# Sheet1.net
KiCad netlist of a schematic drawn in Altium Designer
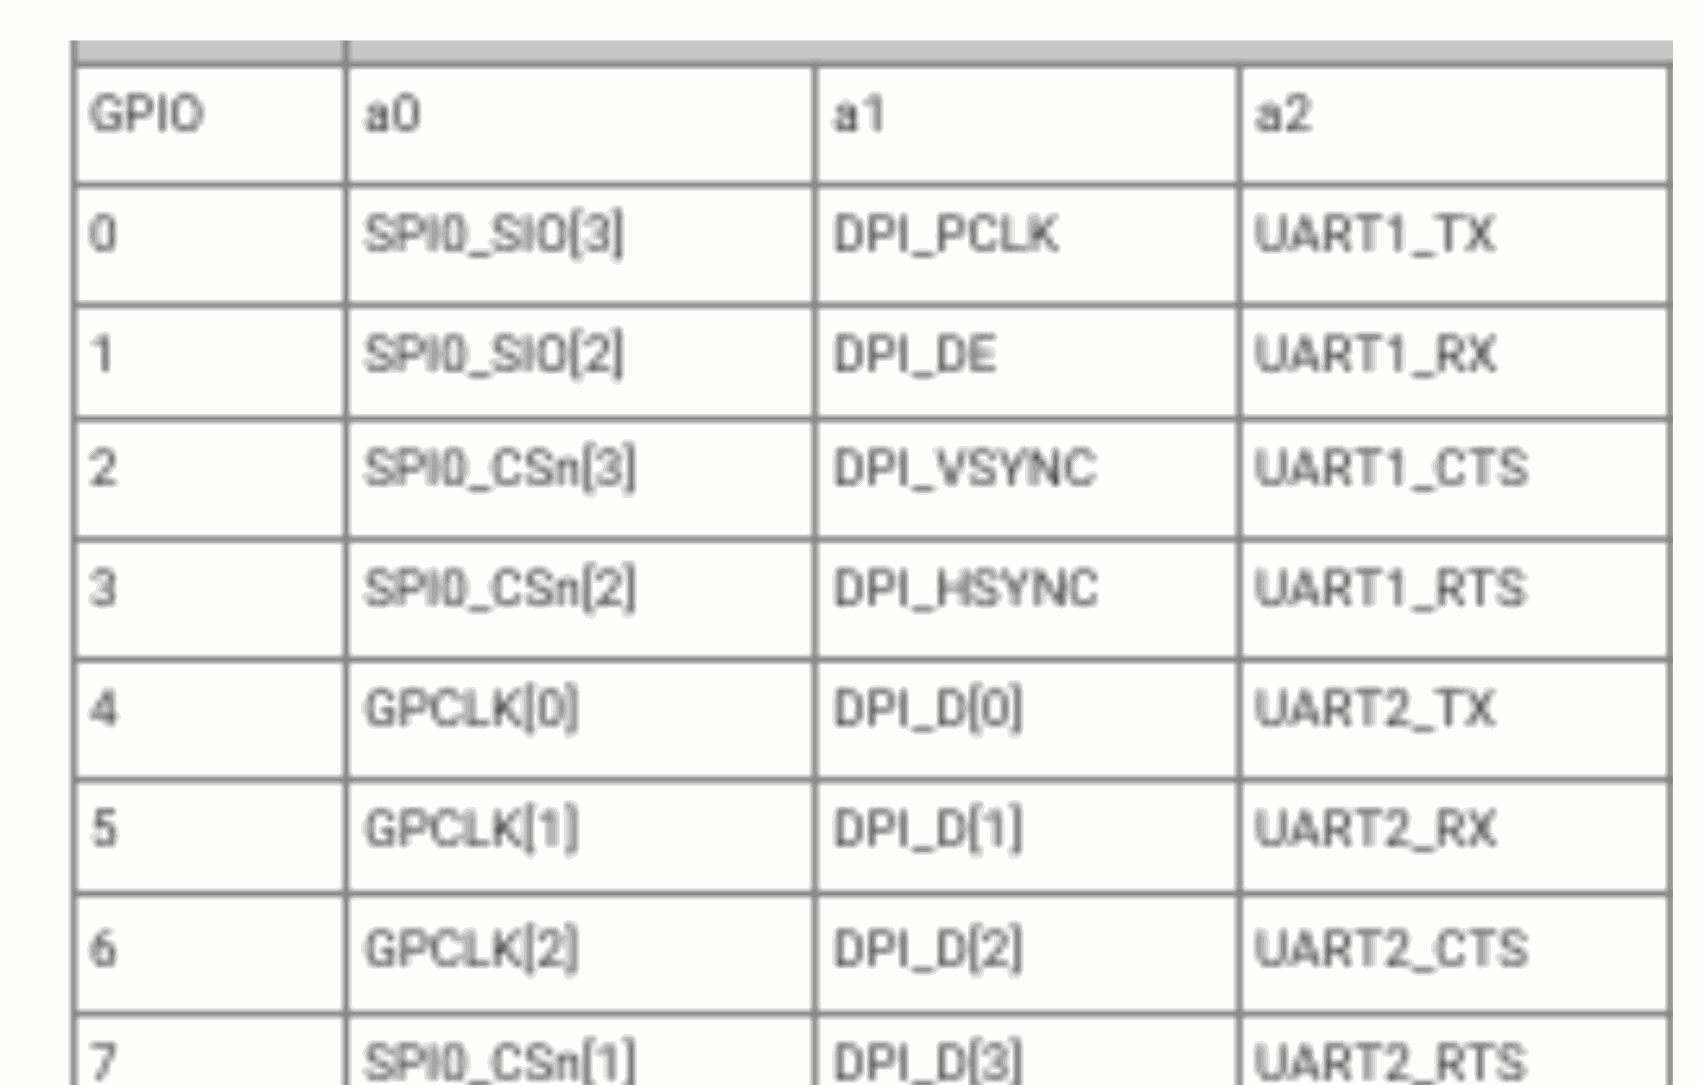
[diagram p0: Sheet1.SchDoc, top left]
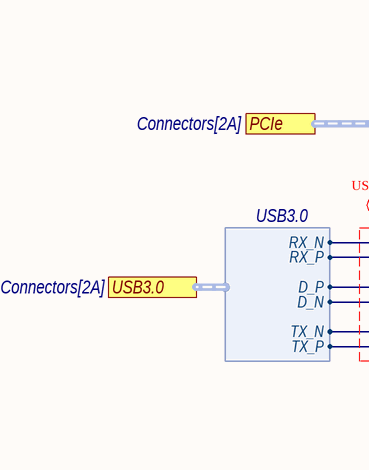
[diagram p1: Sheet1.SchDoc, top middle]
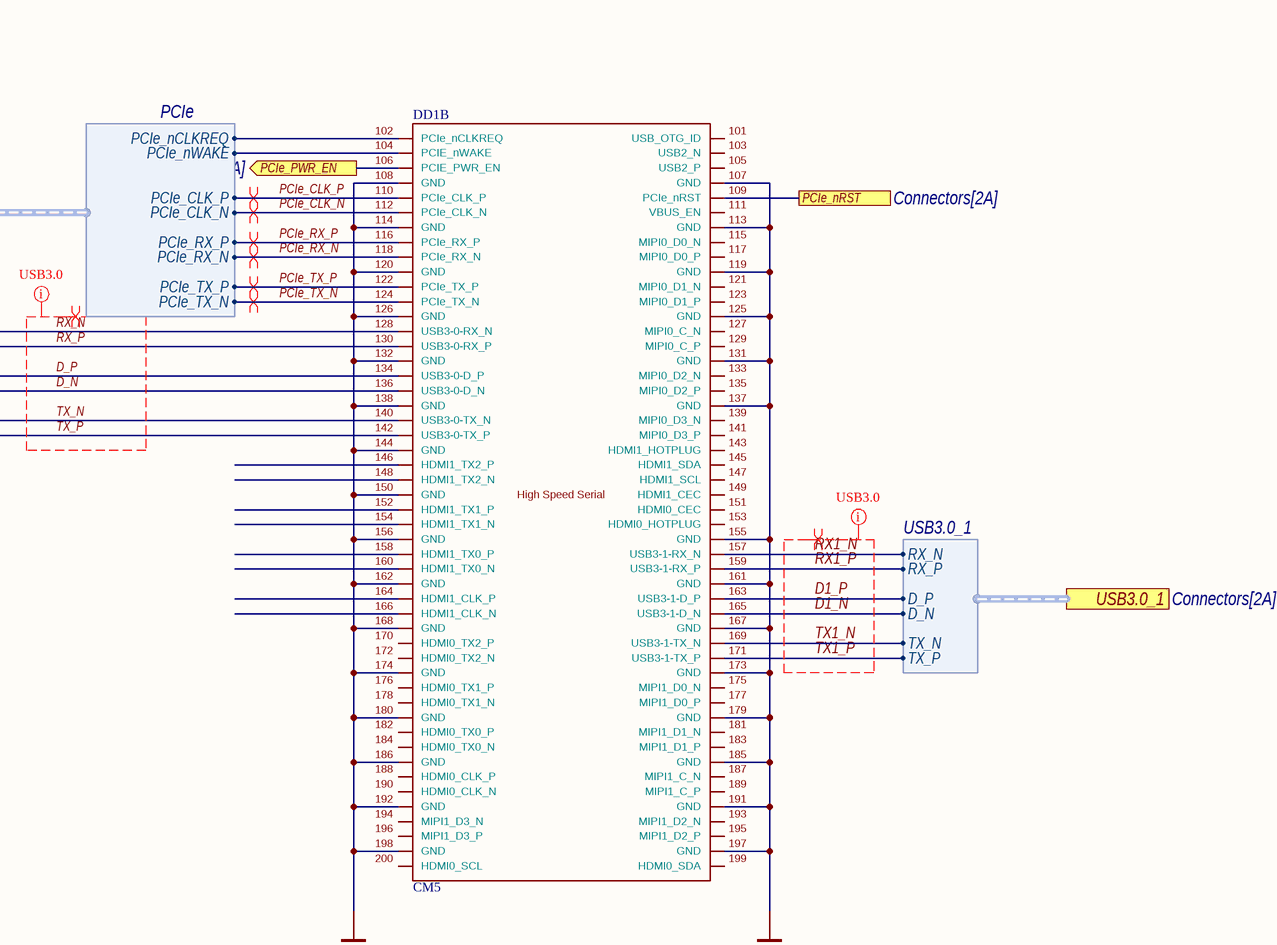
[diagram p2: Sheet1.SchDoc, top right]
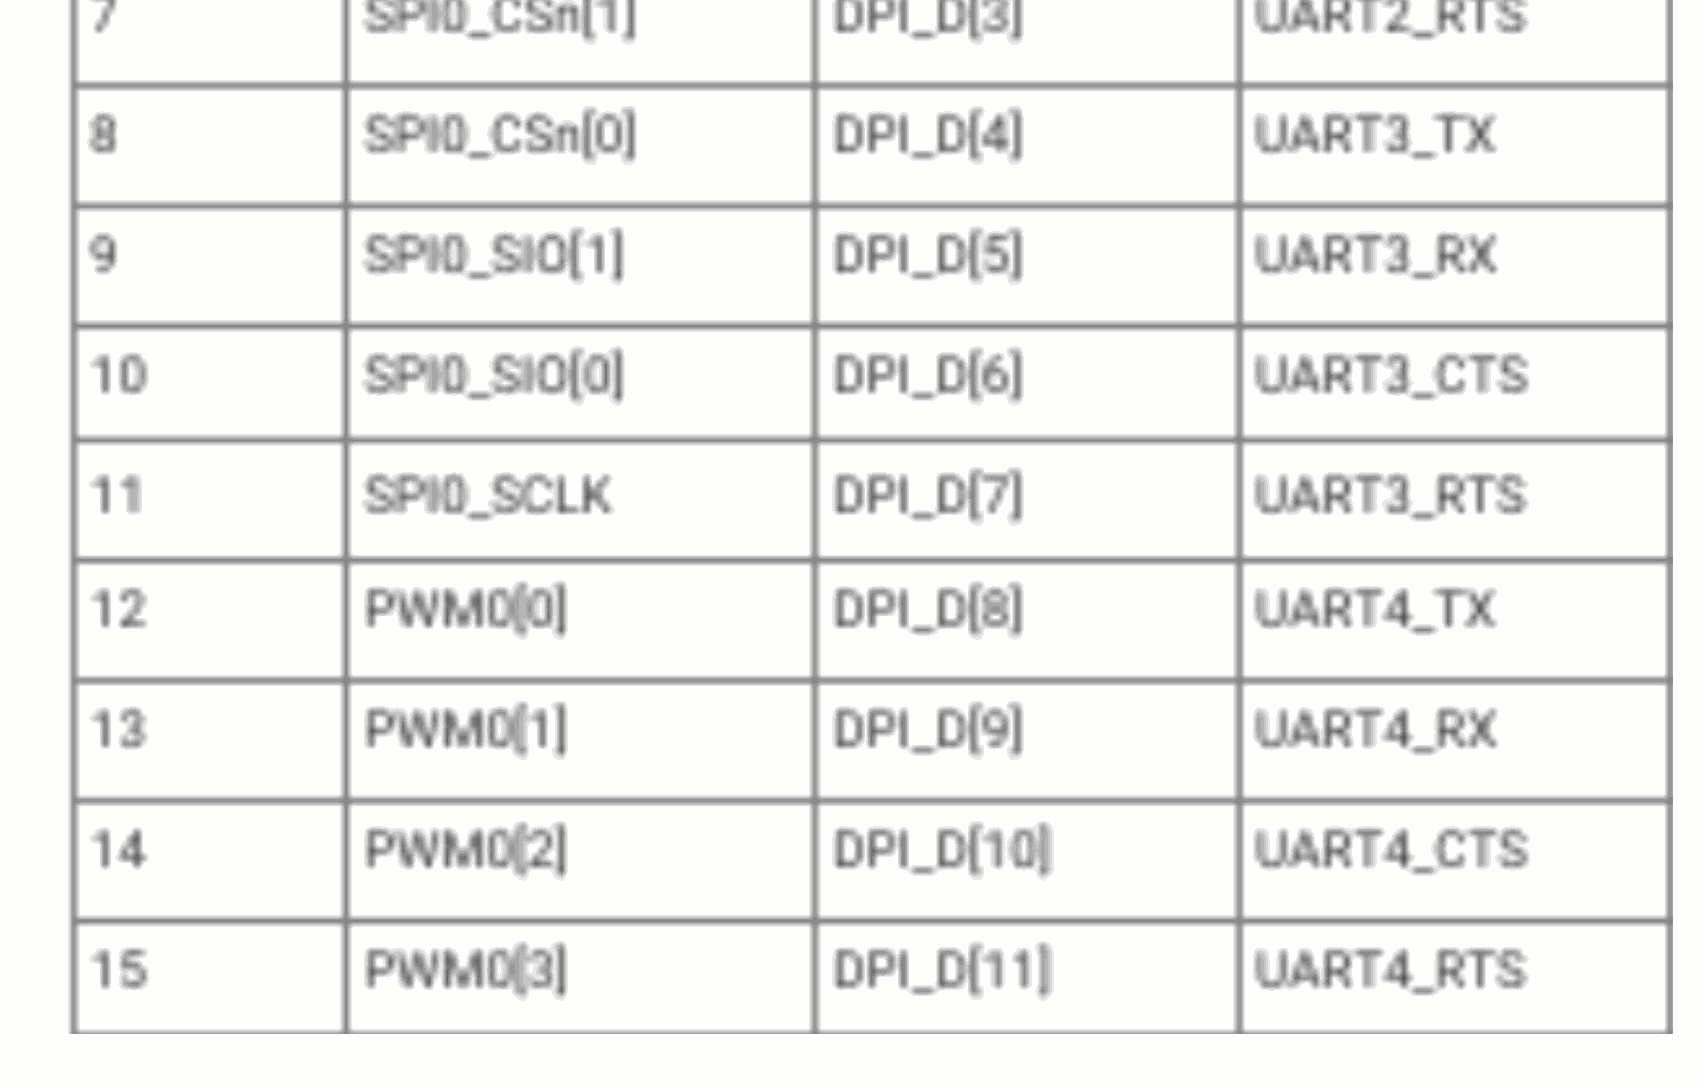
[diagram p3: Sheet1.SchDoc, bottom left]
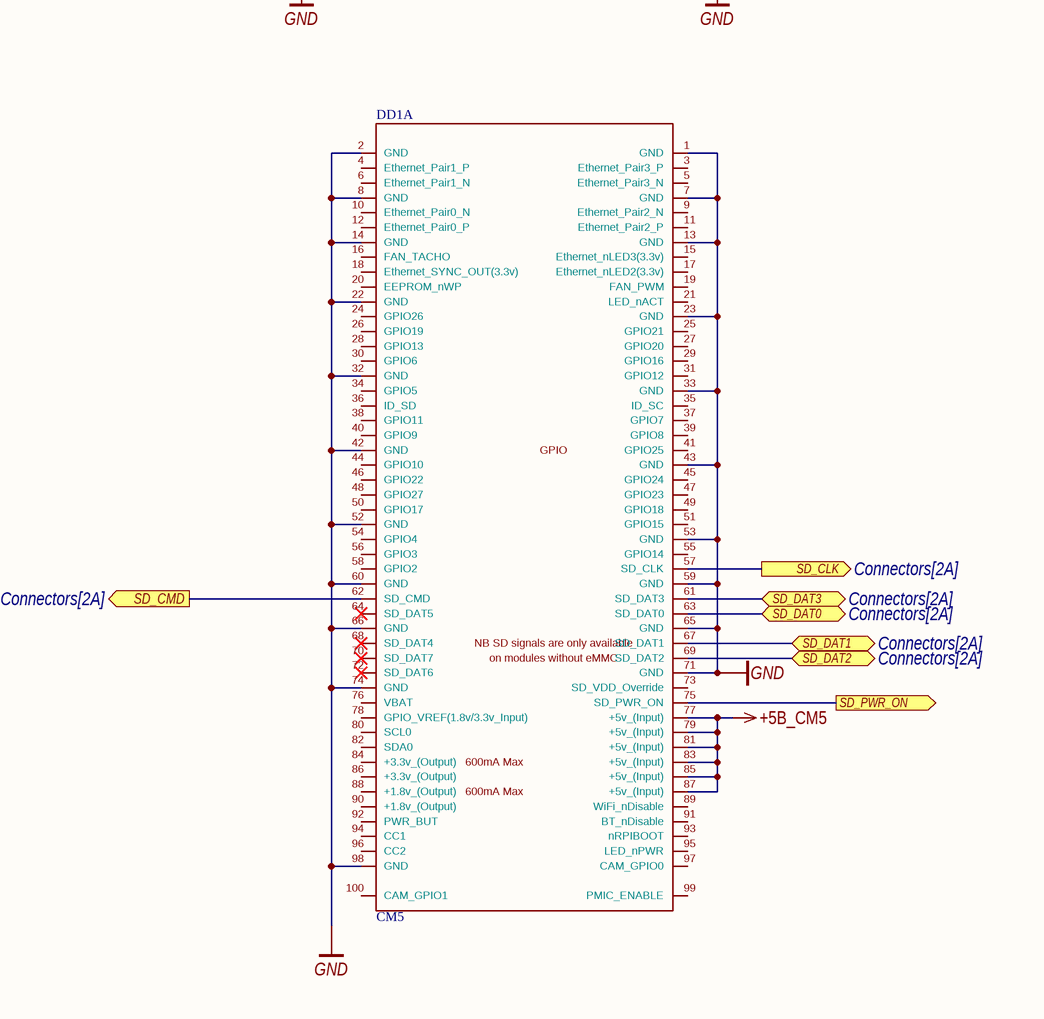
[diagram p4: Sheet1.SchDoc, bottom right]

(export (version "E")
  (design (tool "Eeschema 10.0.6"))
  (components
    (comp (ref "DD1")
      (value "CM5")
      (footprint "CM4-DF40HC(3.0)-100DS-0.4v_3mm_1.5mm")
      (libsource (lib "Hydrolib") (part "CM5"))
    )
  )
  (nets
    (net (code "4") (name "+5В_CM5") (class "Default")
      (node (ref "DD1") (pin "77") (pinfunction "+5v_(Input)_77") (pintype "passive"))
      (node (ref "DD1") (pin "79") (pinfunction "+5v_(Input)_79") (pintype "passive"))
      (node (ref "DD1") (pin "81") (pinfunction "+5v_(Input)_81") (pintype "passive"))
      (node (ref "DD1") (pin "83") (pinfunction "+5v_(Input)_83") (pintype "passive"))
      (node (ref "DD1") (pin "85") (pinfunction "+5v_(Input)_85") (pintype "passive"))
      (node (ref "DD1") (pin "87") (pinfunction "+5v_(Input)_87") (pintype "passive"))
    )
    (net (code "5") (name "/D1_N") (class "Default")
      (node (ref "DD1") (pin "165") (pinfunction "USB3-1-D_N_165") (pintype "passive"))
    )
    (net (code "6") (name "/D1_P") (class "Default")
      (node (ref "DD1") (pin "163") (pinfunction "USB3-1-D_P_163") (pintype "passive"))
    )
    (net (code "7") (name "/D_N") (class "Default")
      (node (ref "DD1") (pin "136") (pinfunction "USB3-0-D_N_136") (pintype "passive"))
    )
    (net (code "8") (name "/D_P") (class "Default")
      (node (ref "DD1") (pin "134") (pinfunction "USB3-0-D_P_134") (pintype "passive"))
    )
    (net (code "9") (name "/PCIe_CLK_N") (class "Default")
      (node (ref "DD1") (pin "112") (pinfunction "PCIe_CLK_N_112") (pintype "passive"))
    )
    (net (code "10") (name "/PCIe_CLK_P") (class "Default")
      (node (ref "DD1") (pin "110") (pinfunction "PCIe_CLK_P_110") (pintype "passive"))
    )
    (net (code "11") (name "/PCIe_PWR_EN") (class "Default")
      (node (ref "DD1") (pin "106") (pinfunction "PCIE_PWR_EN_106") (pintype "passive"))
    )
    (net (code "12") (name "/PCIe_RX_N") (class "Default")
      (node (ref "DD1") (pin "118") (pinfunction "PCIe_RX_N_118") (pintype "passive"))
    )
    (net (code "13") (name "/PCIe_RX_P") (class "Default")
      (node (ref "DD1") (pin "116") (pinfunction "PCIe_RX_P_116") (pintype "passive"))
    )
    (net (code "14") (name "/PCIe_TX_N") (class "Default")
      (node (ref "DD1") (pin "124") (pinfunction "PCIe_TX_N_124") (pintype "passive"))
    )
    (net (code "15") (name "/PCIe_TX_P") (class "Default")
      (node (ref "DD1") (pin "122") (pinfunction "PCIe_TX_P_122") (pintype "passive"))
    )
    (net (code "16") (name "/PCIe_nCLKREQ") (class "Default")
      (node (ref "DD1") (pin "102") (pinfunction "PCIe_nCLKREQ_102") (pintype "passive"))
    )
    (net (code "17") (name "/PCIe_nRST") (class "Default")
      (node (ref "DD1") (pin "109") (pinfunction "PCIe_nRST_109") (pintype "passive"))
    )
    (net (code "18") (name "/PCIe_nWAKE") (class "Default")
      (node (ref "DD1") (pin "104") (pinfunction "PCIE_nWAKE_104") (pintype "passive"))
    )
    (net (code "19") (name "/RX1_N") (class "Default")
      (node (ref "DD1") (pin "157") (pinfunction "USB3-1-RX_N_157") (pintype "passive"))
    )
    (net (code "20") (name "/RX1_P") (class "Default")
      (node (ref "DD1") (pin "159") (pinfunction "USB3-1-RX_P_159") (pintype "passive"))
    )
    (net (code "21") (name "/RX_N") (class "Default")
      (node (ref "DD1") (pin "128") (pinfunction "USB3-0-RX_N_128") (pintype "passive"))
    )
    (net (code "22") (name "/RX_P") (class "Default")
      (node (ref "DD1") (pin "130") (pinfunction "USB3-0-RX_P_130") (pintype "passive"))
    )
    (net (code "23") (name "/SD_CLK") (class "Default")
      (node (ref "DD1") (pin "57") (pinfunction "SD_CLK_57") (pintype "passive"))
    )
    (net (code "24") (name "/SD_CMD") (class "Default")
      (node (ref "DD1") (pin "62") (pinfunction "SD_CMD_62") (pintype "passive"))
    )
    (net (code "25") (name "/SD_DAT0") (class "Default")
      (node (ref "DD1") (pin "63") (pinfunction "SD_DAT0_63") (pintype "passive"))
    )
    (net (code "26") (name "/SD_DAT1") (class "Default")
      (node (ref "DD1") (pin "67") (pinfunction "SD_DAT1_67") (pintype "passive"))
    )
    (net (code "27") (name "/SD_DAT2") (class "Default")
      (node (ref "DD1") (pin "69") (pinfunction "SD_DAT2_69") (pintype "passive"))
    )
    (net (code "28") (name "/SD_DAT3") (class "Default")
      (node (ref "DD1") (pin "61") (pinfunction "SD_DAT3_61") (pintype "passive"))
    )
    (net (code "29") (name "/SD_PWR_ON") (class "Default")
      (node (ref "DD1") (pin "75") (pinfunction "SD_PWR_ON_75") (pintype "passive"))
    )
    (net (code "30") (name "/TX1_N") (class "Default")
      (node (ref "DD1") (pin "169") (pinfunction "USB3-1-TX_N_169") (pintype "passive"))
    )
    (net (code "31") (name "/TX1_P") (class "Default")
      (node (ref "DD1") (pin "171") (pinfunction "USB3-1-TX_P_171") (pintype "passive"))
    )
    (net (code "32") (name "/TX_N") (class "Default")
      (node (ref "DD1") (pin "140") (pinfunction "USB3-0-TX_N_140") (pintype "passive"))
    )
    (net (code "33") (name "/TX_P") (class "Default")
      (node (ref "DD1") (pin "142") (pinfunction "USB3-0-TX_P_142") (pintype "passive"))
    )
    (net (code "37") (name "GND") (class "Default")
      (node (ref "DD1") (pin "1") (pinfunction "GND_1") (pintype "passive"))
      (node (ref "DD1") (pin "107") (pinfunction "GND_107") (pintype "passive"))
      (node (ref "DD1") (pin "108") (pinfunction "GND_108") (pintype "passive"))
      (node (ref "DD1") (pin "113") (pinfunction "GND_113") (pintype "passive"))
      (node (ref "DD1") (pin "114") (pinfunction "GND_114") (pintype "passive"))
      (node (ref "DD1") (pin "119") (pinfunction "GND_119") (pintype "passive"))
      (node (ref "DD1") (pin "120") (pinfunction "GND_120") (pintype "passive"))
      (node (ref "DD1") (pin "125") (pinfunction "GND_125") (pintype "passive"))
      (node (ref "DD1") (pin "126") (pinfunction "GND_126") (pintype "passive"))
      (node (ref "DD1") (pin "13") (pinfunction "GND_13") (pintype "passive"))
      (node (ref "DD1") (pin "131") (pinfunction "GND_131") (pintype "passive"))
      (node (ref "DD1") (pin "132") (pinfunction "GND_132") (pintype "passive"))
      (node (ref "DD1") (pin "137") (pinfunction "GND_137") (pintype "passive"))
      (node (ref "DD1") (pin "138") (pinfunction "GND_138") (pintype "passive"))
      (node (ref "DD1") (pin "14") (pinfunction "GND_14") (pintype "passive"))
      (node (ref "DD1") (pin "144") (pinfunction "GND_144") (pintype "passive"))
      (node (ref "DD1") (pin "150") (pinfunction "GND_150") (pintype "passive"))
      (node (ref "DD1") (pin "155") (pinfunction "GND_155") (pintype "passive"))
      (node (ref "DD1") (pin "156") (pinfunction "GND_156") (pintype "passive"))
      (node (ref "DD1") (pin "161") (pinfunction "GND_161") (pintype "passive"))
      (node (ref "DD1") (pin "162") (pinfunction "GND_162") (pintype "passive"))
      (node (ref "DD1") (pin "167") (pinfunction "GND_167") (pintype "passive"))
      (node (ref "DD1") (pin "168") (pinfunction "GND_168") (pintype "passive"))
      (node (ref "DD1") (pin "173") (pinfunction "GND_173") (pintype "passive"))
      (node (ref "DD1") (pin "174") (pinfunction "GND_174") (pintype "passive"))
      (node (ref "DD1") (pin "179") (pinfunction "GND_179") (pintype "passive"))
      (node (ref "DD1") (pin "180") (pinfunction "GND_180") (pintype "passive"))
      (node (ref "DD1") (pin "185") (pinfunction "GND_185") (pintype "passive"))
      (node (ref "DD1") (pin "186") (pinfunction "GND_186") (pintype "passive"))
      (node (ref "DD1") (pin "191") (pinfunction "GND_191") (pintype "passive"))
      (node (ref "DD1") (pin "192") (pinfunction "GND_192") (pintype "passive"))
      (node (ref "DD1") (pin "197") (pinfunction "GND_197") (pintype "passive"))
      (node (ref "DD1") (pin "198") (pinfunction "GND_198") (pintype "passive"))
      (node (ref "DD1") (pin "2") (pinfunction "GND_2") (pintype "passive"))
      (node (ref "DD1") (pin "22") (pinfunction "GND_22") (pintype "passive"))
      (node (ref "DD1") (pin "23") (pinfunction "GND_23") (pintype "passive"))
      (node (ref "DD1") (pin "32") (pinfunction "GND_32") (pintype "passive"))
      (node (ref "DD1") (pin "33") (pinfunction "GND_33") (pintype "passive"))
      (node (ref "DD1") (pin "42") (pinfunction "GND_42") (pintype "passive"))
      (node (ref "DD1") (pin "43") (pinfunction "GND_43") (pintype "passive"))
      (node (ref "DD1") (pin "52") (pinfunction "GND_52") (pintype "passive"))
      (node (ref "DD1") (pin "53") (pinfunction "GND_53") (pintype "passive"))
      (node (ref "DD1") (pin "59") (pinfunction "GND_59") (pintype "passive"))
      (node (ref "DD1") (pin "60") (pinfunction "GND_60") (pintype "passive"))
      (node (ref "DD1") (pin "65") (pinfunction "GND_65") (pintype "passive"))
      (node (ref "DD1") (pin "66") (pinfunction "GND_66") (pintype "passive"))
      (node (ref "DD1") (pin "7") (pinfunction "GND_7") (pintype "passive"))
      (node (ref "DD1") (pin "71") (pinfunction "GND_71") (pintype "passive"))
      (node (ref "DD1") (pin "74") (pinfunction "GND_74") (pintype "passive"))
      (node (ref "DD1") (pin "8") (pinfunction "GND_8") (pintype "passive"))
      (node (ref "DD1") (pin "98") (pinfunction "GND_98") (pintype "passive"))
    )
    (net (code "38") (name "unconnected-(DD1A-+1.8v_(Output)-Pad88)") (class "Default")
      (node (ref "DD1") (pin "88") (pinfunction "+1.8v_(Output)_88") (pintype "passive"))
    )
    (net (code "39") (name "unconnected-(DD1A-+1.8v_(Output)-Pad90)") (class "Default")
      (node (ref "DD1") (pin "90") (pinfunction "+1.8v_(Output)_90") (pintype "passive"))
    )
    (net (code "40") (name "unconnected-(DD1A-+3.3v_(Output)-Pad84)") (class "Default")
      (node (ref "DD1") (pin "84") (pinfunction "+3.3v_(Output)_84") (pintype "passive"))
    )
    (net (code "41") (name "unconnected-(DD1A-+3.3v_(Output)-Pad86)") (class "Default")
      (node (ref "DD1") (pin "86") (pinfunction "+3.3v_(Output)_86") (pintype "passive"))
    )
    (net (code "42") (name "unconnected-(DD1A-BT_nDisable-Pad91)") (class "Default")
      (node (ref "DD1") (pin "91") (pinfunction "BT_nDisable_91") (pintype "passive"))
    )
    (net (code "43") (name "unconnected-(DD1A-CAM_GPIO0-Pad97)") (class "Default")
      (node (ref "DD1") (pin "97") (pinfunction "CAM_GPIO0_97") (pintype "passive"))
    )
    (net (code "44") (name "unconnected-(DD1A-CAM_GPIO1-Pad100)") (class "Default")
      (node (ref "DD1") (pin "100") (pinfunction "CAM_GPIO1_100") (pintype "passive"))
    )
    (net (code "45") (name "unconnected-(DD1A-CC1-Pad94)") (class "Default")
      (node (ref "DD1") (pin "94") (pinfunction "CC1_94") (pintype "passive"))
    )
    (net (code "46") (name "unconnected-(DD1A-CC2-Pad96)") (class "Default")
      (node (ref "DD1") (pin "96") (pinfunction "CC2_96") (pintype "passive"))
    )
    (net (code "47") (name "unconnected-(DD1A-EEPROM_nWP-Pad20)") (class "Default")
      (node (ref "DD1") (pin "20") (pinfunction "EEPROM_nWP_20") (pintype "passive"))
    )
    (net (code "48") (name "unconnected-(DD1A-Ethernet_Pair0_N-Pad10)") (class "Default")
      (node (ref "DD1") (pin "10") (pinfunction "Ethernet_Pair0_N_10") (pintype "passive"))
    )
    (net (code "49") (name "unconnected-(DD1A-Ethernet_Pair0_P-Pad12)") (class "Default")
      (node (ref "DD1") (pin "12") (pinfunction "Ethernet_Pair0_P_12") (pintype "passive"))
    )
    (net (code "50") (name "unconnected-(DD1A-Ethernet_Pair1_N-Pad6)") (class "Default")
      (node (ref "DD1") (pin "6") (pinfunction "Ethernet_Pair1_N_6") (pintype "passive"))
    )
    (net (code "51") (name "unconnected-(DD1A-Ethernet_Pair1_P-Pad4)") (class "Default")
      (node (ref "DD1") (pin "4") (pinfunction "Ethernet_Pair1_P_4") (pintype "passive"))
    )
    (net (code "52") (name "unconnected-(DD1A-Ethernet_Pair2_N-Pad9)") (class "Default")
      (node (ref "DD1") (pin "9") (pinfunction "Ethernet_Pair2_N_9") (pintype "passive"))
    )
    (net (code "53") (name "unconnected-(DD1A-Ethernet_Pair2_P-Pad11)") (class "Default")
      (node (ref "DD1") (pin "11") (pinfunction "Ethernet_Pair2_P_11") (pintype "passive"))
    )
    (net (code "54") (name "unconnected-(DD1A-Ethernet_Pair3_N-Pad5)") (class "Default")
      (node (ref "DD1") (pin "5") (pinfunction "Ethernet_Pair3_N_5") (pintype "passive"))
    )
    (net (code "55") (name "unconnected-(DD1A-Ethernet_Pair3_P-Pad3)") (class "Default")
      (node (ref "DD1") (pin "3") (pinfunction "Ethernet_Pair3_P_3") (pintype "passive"))
    )
    (net (code "56") (name "unconnected-(DD1A-Ethernet_SYNC_OUT(3.3v)-Pad18)") (class "Default")
      (node (ref "DD1") (pin "18") (pinfunction "Ethernet_SYNC_OUT(3.3v)_18") (pintype "passive"))
    )
    (net (code "57") (name "unconnected-(DD1A-Ethernet_nLED2(3.3v)-Pad17)") (class "Default")
      (node (ref "DD1") (pin "17") (pinfunction "Ethernet_nLED2(3.3v)_17") (pintype "passive"))
    )
    (net (code "58") (name "unconnected-(DD1A-Ethernet_nLED3(3.3v)-Pad15)") (class "Default")
      (node (ref "DD1") (pin "15") (pinfunction "Ethernet_nLED3(3.3v)_15") (pintype "passive"))
    )
    (net (code "59") (name "unconnected-(DD1A-FAN_PWM-Pad19)") (class "Default")
      (node (ref "DD1") (pin "19") (pinfunction "FAN_PWM_19") (pintype "passive"))
    )
    (net (code "60") (name "unconnected-(DD1A-FAN_TACHO-Pad16)") (class "Default")
      (node (ref "DD1") (pin "16") (pinfunction "FAN_TACHO_16") (pintype "passive"))
    )
    (net (code "61") (name "unconnected-(DD1A-GPIO2-Pad58)") (class "Default")
      (node (ref "DD1") (pin "58") (pinfunction "GPIO2_58") (pintype "passive"))
    )
    (net (code "62") (name "unconnected-(DD1A-GPIO3-Pad56)") (class "Default")
      (node (ref "DD1") (pin "56") (pinfunction "GPIO3_56") (pintype "passive"))
    )
    (net (code "63") (name "unconnected-(DD1A-GPIO4-Pad54)") (class "Default")
      (node (ref "DD1") (pin "54") (pinfunction "GPIO4_54") (pintype "passive"))
    )
    (net (code "64") (name "unconnected-(DD1A-GPIO5-Pad34)") (class "Default")
      (node (ref "DD1") (pin "34") (pinfunction "GPIO5_34") (pintype "passive"))
    )
    (net (code "65") (name "unconnected-(DD1A-GPIO6-Pad30)") (class "Default")
      (node (ref "DD1") (pin "30") (pinfunction "GPIO6_30") (pintype "passive"))
    )
    (net (code "66") (name "unconnected-(DD1A-GPIO7-Pad37)") (class "Default")
      (node (ref "DD1") (pin "37") (pinfunction "GPIO7_37") (pintype "passive"))
    )
    (net (code "67") (name "unconnected-(DD1A-GPIO8-Pad39)") (class "Default")
      (node (ref "DD1") (pin "39") (pinfunction "GPIO8_39") (pintype "passive"))
    )
    (net (code "68") (name "unconnected-(DD1A-GPIO9-Pad40)") (class "Default")
      (node (ref "DD1") (pin "40") (pinfunction "GPIO9_40") (pintype "passive"))
    )
    (net (code "69") (name "unconnected-(DD1A-GPIO10-Pad44)") (class "Default")
      (node (ref "DD1") (pin "44") (pinfunction "GPIO10_44") (pintype "passive"))
    )
    (net (code "70") (name "unconnected-(DD1A-GPIO11-Pad38)") (class "Default")
      (node (ref "DD1") (pin "38") (pinfunction "GPIO11_38") (pintype "passive"))
    )
    (net (code "71") (name "unconnected-(DD1A-GPIO12-Pad31)") (class "Default")
      (node (ref "DD1") (pin "31") (pinfunction "GPIO12_31") (pintype "passive"))
    )
    (net (code "72") (name "unconnected-(DD1A-GPIO13-Pad28)") (class "Default")
      (node (ref "DD1") (pin "28") (pinfunction "GPIO13_28") (pintype "passive"))
    )
    (net (code "73") (name "unconnected-(DD1A-GPIO14-Pad55)") (class "Default")
      (node (ref "DD1") (pin "55") (pinfunction "GPIO14_55") (pintype "passive"))
    )
    (net (code "74") (name "unconnected-(DD1A-GPIO15-Pad51)") (class "Default")
      (node (ref "DD1") (pin "51") (pinfunction "GPIO15_51") (pintype "passive"))
    )
    (net (code "75") (name "unconnected-(DD1A-GPIO16-Pad29)") (class "Default")
      (node (ref "DD1") (pin "29") (pinfunction "GPIO16_29") (pintype "passive"))
    )
    (net (code "76") (name "unconnected-(DD1A-GPIO17-Pad50)") (class "Default")
      (node (ref "DD1") (pin "50") (pinfunction "GPIO17_50") (pintype "passive"))
    )
    (net (code "77") (name "unconnected-(DD1A-GPIO18-Pad49)") (class "Default")
      (node (ref "DD1") (pin "49") (pinfunction "GPIO18_49") (pintype "passive"))
    )
    (net (code "78") (name "unconnected-(DD1A-GPIO19-Pad26)") (class "Default")
      (node (ref "DD1") (pin "26") (pinfunction "GPIO19_26") (pintype "passive"))
    )
    (net (code "79") (name "unconnected-(DD1A-GPIO20-Pad27)") (class "Default")
      (node (ref "DD1") (pin "27") (pinfunction "GPIO20_27") (pintype "passive"))
    )
    (net (code "80") (name "unconnected-(DD1A-GPIO21-Pad25)") (class "Default")
      (node (ref "DD1") (pin "25") (pinfunction "GPIO21_25") (pintype "passive"))
    )
    (net (code "81") (name "unconnected-(DD1A-GPIO22-Pad46)") (class "Default")
      (node (ref "DD1") (pin "46") (pinfunction "GPIO22_46") (pintype "passive"))
    )
    (net (code "82") (name "unconnected-(DD1A-GPIO23-Pad47)") (class "Default")
      (node (ref "DD1") (pin "47") (pinfunction "GPIO23_47") (pintype "passive"))
    )
    (net (code "83") (name "unconnected-(DD1A-GPIO24-Pad45)") (class "Default")
      (node (ref "DD1") (pin "45") (pinfunction "GPIO24_45") (pintype "passive"))
    )
    (net (code "84") (name "unconnected-(DD1A-GPIO25-Pad41)") (class "Default")
      (node (ref "DD1") (pin "41") (pinfunction "GPIO25_41") (pintype "passive"))
    )
    (net (code "85") (name "unconnected-(DD1A-GPIO26-Pad24)") (class "Default")
      (node (ref "DD1") (pin "24") (pinfunction "GPIO26_24") (pintype "passive"))
    )
    (net (code "86") (name "unconnected-(DD1A-GPIO27-Pad48)") (class "Default")
      (node (ref "DD1") (pin "48") (pinfunction "GPIO27_48") (pintype "passive"))
    )
    (net (code "87") (name "unconnected-(DD1A-GPIO_VREF(1.8v{slash}3.3v_Input)-Pad78)") (class "Default")
      (node (ref "DD1") (pin "78") (pinfunction "GPIO_VREF(1.8v/3.3v_Input)_78") (pintype "passive"))
    )
    (net (code "88") (name "unconnected-(DD1A-ID_SC-Pad35)") (class "Default")
      (node (ref "DD1") (pin "35") (pinfunction "ID_SC_35") (pintype "passive"))
    )
    (net (code "89") (name "unconnected-(DD1A-ID_SD-Pad36)") (class "Default")
      (node (ref "DD1") (pin "36") (pinfunction "ID_SD_36") (pintype "passive"))
    )
    (net (code "90") (name "unconnected-(DD1A-LED_nACT-Pad21)") (class "Default")
      (node (ref "DD1") (pin "21") (pinfunction "LED_nACT_21") (pintype "passive"))
    )
    (net (code "91") (name "unconnected-(DD1A-LED_nPWR-Pad95)") (class "Default")
      (node (ref "DD1") (pin "95") (pinfunction "LED_nPWR_95") (pintype "passive"))
    )
    (net (code "92") (name "unconnected-(DD1A-PMIC_ENABLE-Pad99)") (class "Default")
      (node (ref "DD1") (pin "99") (pinfunction "PMIC_ENABLE_99") (pintype "passive"))
    )
    (net (code "93") (name "unconnected-(DD1A-PWR_BUT-Pad92)") (class "Default")
      (node (ref "DD1") (pin "92") (pinfunction "PWR_BUT_92") (pintype "passive"))
    )
    (net (code "94") (name "unconnected-(DD1A-SCL0-Pad80)") (class "Default")
      (node (ref "DD1") (pin "80") (pinfunction "SCL0_80") (pintype "passive"))
    )
    (net (code "95") (name "unconnected-(DD1A-SDA0-Pad82)") (class "Default")
      (node (ref "DD1") (pin "82") (pinfunction "SDA0_82") (pintype "passive"))
    )
    (net (code "96") (name "unconnected-(DD1A-SD_DAT4-Pad68)") (class "Default")
      (node (ref "DD1") (pin "68") (pinfunction "SD_DAT4_68") (pintype "passive+no_connect"))
    )
    (net (code "97") (name "unconnected-(DD1A-SD_DAT5-Pad64)") (class "Default")
      (node (ref "DD1") (pin "64") (pinfunction "SD_DAT5_64") (pintype "passive+no_connect"))
    )
    (net (code "98") (name "unconnected-(DD1A-SD_DAT6-Pad72)") (class "Default")
      (node (ref "DD1") (pin "72") (pinfunction "SD_DAT6_72") (pintype "passive+no_connect"))
    )
    (net (code "99") (name "unconnected-(DD1A-SD_DAT7-Pad70)") (class "Default")
      (node (ref "DD1") (pin "70") (pinfunction "SD_DAT7_70") (pintype "passive+no_connect"))
    )
    (net (code "100") (name "unconnected-(DD1A-SD_VDD_Override-Pad73)") (class "Default")
      (node (ref "DD1") (pin "73") (pinfunction "SD_VDD_Override_73") (pintype "passive"))
    )
    (net (code "101") (name "unconnected-(DD1A-VBAT-Pad76)") (class "Default")
      (node (ref "DD1") (pin "76") (pinfunction "VBAT_76") (pintype "passive"))
    )
    (net (code "102") (name "unconnected-(DD1A-WiFi_nDisable-Pad89)") (class "Default")
      (node (ref "DD1") (pin "89") (pinfunction "WiFi_nDisable_89") (pintype "passive"))
    )
    (net (code "103") (name "unconnected-(DD1A-nRPIBOOT-Pad93)") (class "Default")
      (node (ref "DD1") (pin "93") (pinfunction "nRPIBOOT_93") (pintype "passive"))
    )
    (net (code "104") (name "unconnected-(DD1B-HDMI0_CEC-Pad151)") (class "Default")
      (node (ref "DD1") (pin "151") (pinfunction "HDMI0_CEC_151") (pintype "passive"))
    )
    (net (code "105") (name "unconnected-(DD1B-HDMI0_CLK_N-Pad190)") (class "Default")
      (node (ref "DD1") (pin "190") (pinfunction "HDMI0_CLK_N_190") (pintype "passive"))
    )
    (net (code "106") (name "unconnected-(DD1B-HDMI0_CLK_P-Pad188)") (class "Default")
      (node (ref "DD1") (pin "188") (pinfunction "HDMI0_CLK_P_188") (pintype "passive"))
    )
    (net (code "107") (name "unconnected-(DD1B-HDMI0_HOTPLUG-Pad153)") (class "Default")
      (node (ref "DD1") (pin "153") (pinfunction "HDMI0_HOTPLUG_153") (pintype "passive"))
    )
    (net (code "108") (name "unconnected-(DD1B-HDMI0_SCL-Pad200)") (class "Default")
      (node (ref "DD1") (pin "200") (pinfunction "HDMI0_SCL_200") (pintype "passive"))
    )
    (net (code "109") (name "unconnected-(DD1B-HDMI0_SDA-Pad199)") (class "Default")
      (node (ref "DD1") (pin "199") (pinfunction "HDMI0_SDA_199") (pintype "passive"))
    )
    (net (code "110") (name "unconnected-(DD1B-HDMI0_TX0_N-Pad184)") (class "Default")
      (node (ref "DD1") (pin "184") (pinfunction "HDMI0_TX0_N_184") (pintype "passive"))
    )
    (net (code "111") (name "unconnected-(DD1B-HDMI0_TX0_P-Pad182)") (class "Default")
      (node (ref "DD1") (pin "182") (pinfunction "HDMI0_TX0_P_182") (pintype "passive"))
    )
    (net (code "112") (name "unconnected-(DD1B-HDMI0_TX1_N-Pad178)") (class "Default")
      (node (ref "DD1") (pin "178") (pinfunction "HDMI0_TX1_N_178") (pintype "passive"))
    )
    (net (code "113") (name "unconnected-(DD1B-HDMI0_TX1_P-Pad176)") (class "Default")
      (node (ref "DD1") (pin "176") (pinfunction "HDMI0_TX1_P_176") (pintype "passive"))
    )
    (net (code "114") (name "unconnected-(DD1B-HDMI0_TX2_N-Pad172)") (class "Default")
      (node (ref "DD1") (pin "172") (pinfunction "HDMI0_TX2_N_172") (pintype "passive"))
    )
    (net (code "115") (name "unconnected-(DD1B-HDMI0_TX2_P-Pad170)") (class "Default")
      (node (ref "DD1") (pin "170") (pinfunction "HDMI0_TX2_P_170") (pintype "passive"))
    )
    (net (code "116") (name "unconnected-(DD1B-HDMI1_CEC-Pad149)") (class "Default")
      (node (ref "DD1") (pin "149") (pinfunction "HDMI1_CEC_149") (pintype "passive"))
    )
    (net (code "117") (name "unconnected-(DD1B-HDMI1_CLK_N-Pad166)") (class "Default")
      (node (ref "DD1") (pin "166") (pinfunction "HDMI1_CLK_N_166") (pintype "passive"))
    )
    (net (code "118") (name "unconnected-(DD1B-HDMI1_CLK_P-Pad164)") (class "Default")
      (node (ref "DD1") (pin "164") (pinfunction "HDMI1_CLK_P_164") (pintype "passive"))
    )
    (net (code "119") (name "unconnected-(DD1B-HDMI1_HOTPLUG-Pad143)") (class "Default")
      (node (ref "DD1") (pin "143") (pinfunction "HDMI1_HOTPLUG_143") (pintype "passive"))
    )
    (net (code "120") (name "unconnected-(DD1B-HDMI1_SCL-Pad147)") (class "Default")
      (node (ref "DD1") (pin "147") (pinfunction "HDMI1_SCL_147") (pintype "passive"))
    )
    (net (code "121") (name "unconnected-(DD1B-HDMI1_SDA-Pad145)") (class "Default")
      (node (ref "DD1") (pin "145") (pinfunction "HDMI1_SDA_145") (pintype "passive"))
    )
    (net (code "122") (name "unconnected-(DD1B-HDMI1_TX0_N-Pad160)") (class "Default")
      (node (ref "DD1") (pin "160") (pinfunction "HDMI1_TX0_N_160") (pintype "passive"))
    )
    (net (code "123") (name "unconnected-(DD1B-HDMI1_TX0_P-Pad158)") (class "Default")
      (node (ref "DD1") (pin "158") (pinfunction "HDMI1_TX0_P_158") (pintype "passive"))
    )
    (net (code "124") (name "unconnected-(DD1B-HDMI1_TX1_N-Pad154)") (class "Default")
      (node (ref "DD1") (pin "154") (pinfunction "HDMI1_TX1_N_154") (pintype "passive"))
    )
    (net (code "125") (name "unconnected-(DD1B-HDMI1_TX1_P-Pad152)") (class "Default")
      (node (ref "DD1") (pin "152") (pinfunction "HDMI1_TX1_P_152") (pintype "passive"))
    )
    (net (code "126") (name "unconnected-(DD1B-HDMI1_TX2_N-Pad148)") (class "Default")
      (node (ref "DD1") (pin "148") (pinfunction "HDMI1_TX2_N_148") (pintype "passive"))
    )
    (net (code "127") (name "unconnected-(DD1B-HDMI1_TX2_P-Pad146)") (class "Default")
      (node (ref "DD1") (pin "146") (pinfunction "HDMI1_TX2_P_146") (pintype "passive"))
    )
    (net (code "128") (name "unconnected-(DD1B-MIPI0_C_N-Pad127)") (class "Default")
      (node (ref "DD1") (pin "127") (pinfunction "MIPI0_C_N_127") (pintype "passive"))
    )
    (net (code "129") (name "unconnected-(DD1B-MIPI0_C_P-Pad129)") (class "Default")
      (node (ref "DD1") (pin "129") (pinfunction "MIPI0_C_P_129") (pintype "passive"))
    )
    (net (code "130") (name "unconnected-(DD1B-MIPI0_D0_N-Pad115)") (class "Default")
      (node (ref "DD1") (pin "115") (pinfunction "MIPI0_D0_N_115") (pintype "passive"))
    )
    (net (code "131") (name "unconnected-(DD1B-MIPI0_D0_P-Pad117)") (class "Default")
      (node (ref "DD1") (pin "117") (pinfunction "MIPI0_D0_P_117") (pintype "passive"))
    )
    (net (code "132") (name "unconnected-(DD1B-MIPI0_D1_N-Pad121)") (class "Default")
      (node (ref "DD1") (pin "121") (pinfunction "MIPI0_D1_N_121") (pintype "passive"))
    )
    (net (code "133") (name "unconnected-(DD1B-MIPI0_D1_P-Pad123)") (class "Default")
      (node (ref "DD1") (pin "123") (pinfunction "MIPI0_D1_P_123") (pintype "passive"))
    )
    (net (code "134") (name "unconnected-(DD1B-MIPI0_D2_N-Pad133)") (class "Default")
      (node (ref "DD1") (pin "133") (pinfunction "MIPI0_D2_N_133") (pintype "passive"))
    )
    (net (code "135") (name "unconnected-(DD1B-MIPI0_D2_P-Pad135)") (class "Default")
      (node (ref "DD1") (pin "135") (pinfunction "MIPI0_D2_P_135") (pintype "passive"))
    )
    (net (code "136") (name "unconnected-(DD1B-MIPI0_D3_N-Pad139)") (class "Default")
      (node (ref "DD1") (pin "139") (pinfunction "MIPI0_D3_N_139") (pintype "passive"))
    )
    (net (code "137") (name "unconnected-(DD1B-MIPI0_D3_P-Pad141)") (class "Default")
      (node (ref "DD1") (pin "141") (pinfunction "MIPI0_D3_P_141") (pintype "passive"))
    )
    (net (code "138") (name "unconnected-(DD1B-MIPI1_C_N-Pad187)") (class "Default")
      (node (ref "DD1") (pin "187") (pinfunction "MIPI1_C_N_187") (pintype "passive"))
    )
    (net (code "139") (name "unconnected-(DD1B-MIPI1_C_P-Pad189)") (class "Default")
      (node (ref "DD1") (pin "189") (pinfunction "MIPI1_C_P_189") (pintype "passive"))
    )
    (net (code "140") (name "unconnected-(DD1B-MIPI1_D0_N-Pad175)") (class "Default")
      (node (ref "DD1") (pin "175") (pinfunction "MIPI1_D0_N_175") (pintype "passive"))
    )
    (net (code "141") (name "unconnected-(DD1B-MIPI1_D0_P-Pad177)") (class "Default")
      (node (ref "DD1") (pin "177") (pinfunction "MIPI1_D0_P_177") (pintype "passive"))
    )
    (net (code "142") (name "unconnected-(DD1B-MIPI1_D1_N-Pad181)") (class "Default")
      (node (ref "DD1") (pin "181") (pinfunction "MIPI1_D1_N_181") (pintype "passive"))
    )
    (net (code "143") (name "unconnected-(DD1B-MIPI1_D1_P-Pad183)") (class "Default")
      (node (ref "DD1") (pin "183") (pinfunction "MIPI1_D1_P_183") (pintype "passive"))
    )
    (net (code "144") (name "unconnected-(DD1B-MIPI1_D2_N-Pad193)") (class "Default")
      (node (ref "DD1") (pin "193") (pinfunction "MIPI1_D2_N_193") (pintype "passive"))
    )
    (net (code "145") (name "unconnected-(DD1B-MIPI1_D2_P-Pad195)") (class "Default")
      (node (ref "DD1") (pin "195") (pinfunction "MIPI1_D2_P_195") (pintype "passive"))
    )
    (net (code "146") (name "unconnected-(DD1B-MIPI1_D3_N-Pad194)") (class "Default")
      (node (ref "DD1") (pin "194") (pinfunction "MIPI1_D3_N_194") (pintype "passive"))
    )
    (net (code "147") (name "unconnected-(DD1B-MIPI1_D3_P-Pad196)") (class "Default")
      (node (ref "DD1") (pin "196") (pinfunction "MIPI1_D3_P_196") (pintype "passive"))
    )
    (net (code "148") (name "unconnected-(DD1B-USB2_N-Pad103)") (class "Default")
      (node (ref "DD1") (pin "103") (pinfunction "USB2_N_103") (pintype "passive"))
    )
    (net (code "149") (name "unconnected-(DD1B-USB2_P-Pad105)") (class "Default")
      (node (ref "DD1") (pin "105") (pinfunction "USB2_P_105") (pintype "passive"))
    )
    (net (code "150") (name "unconnected-(DD1B-USB_OTG_ID-Pad101)") (class "Default")
      (node (ref "DD1") (pin "101") (pinfunction "USB_OTG_ID_101") (pintype "passive"))
    )
    (net (code "151") (name "unconnected-(DD1B-VBUS_EN-Pad111)") (class "Default")
      (node (ref "DD1") (pin "111") (pinfunction "VBUS_EN_111") (pintype "passive"))
    )
  )
)
